# button.net
KiCad netlist of a schematic drawn in EAGLE
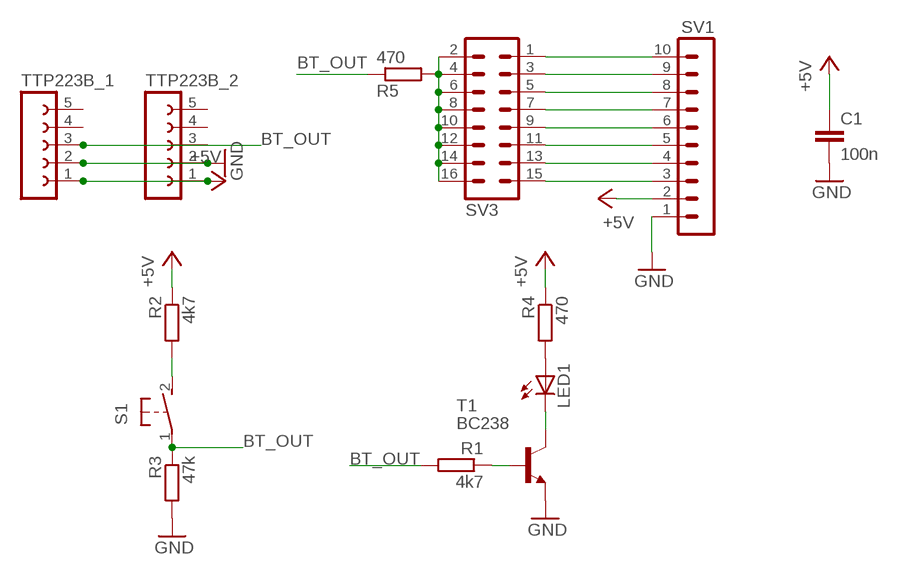
[diagram p0: schematic, sheet 1]

(export (version "E")
  (design (tool "Eeschema 10.0.6"))
  (components
    (comp (ref "C1")
      (value "100n")
      (footprint "eagle-import:C025-024X044")
      (libsource (lib "eagle-import") (part "C-EU025-024X044"))
    )
    (comp (ref "LED1")
      (value "LED5MM")
      (footprint "eagle-import:LED5MM")
      (libsource (lib "eagle-import") (part "LED5MM"))
    )
    (comp (ref "R1")
      (value "4k7")
      (footprint "eagle-import:0309_10")
      (libsource (lib "eagle-import") (part "R-EU_0309/10"))
    )
    (comp (ref "R2")
      (value "4k7")
      (footprint "eagle-import:R0805")
      (libsource (lib "eagle-import") (part "R-EU_R0805"))
    )
    (comp (ref "R3")
      (value "47k")
      (footprint "eagle-import:0414_15")
      (libsource (lib "eagle-import") (part "R-EU_0414/15"))
    )
    (comp (ref "R4")
      (value "470")
      (footprint "eagle-import:0207_7")
      (libsource (lib "eagle-import") (part "R-EU_0207/7"))
    )
    (comp (ref "R5")
      (value "470")
      (footprint "eagle-import:0207_7")
      (libsource (lib "eagle-import") (part "R-EU_0207/7"))
    )
    (comp (ref "S1")
      (value "31-XX")
      (footprint "eagle-import:B3F-31XX")
      (fields (field (name "MPN") "B3F-3100"))
      (libsource (lib "eagle-import") (part "31-XX"))
    )
    (comp (ref "SV1")
      (value "MA10-1W")
      (footprint "eagle-import:MA10-1W")
      (libsource (lib "eagle-import") (part "MA10-1W"))
    )
    (comp (ref "SV3")
      (value "MA08-2")
      (footprint "eagle-import:MA08-2")
      (libsource (lib "eagle-import") (part "MA08-2"))
    )
    (comp (ref "T1")
      (value "BC238")
      (footprint "eagle-import:TO5")
      (libsource (lib "eagle-import") (part "-NPN-TO5"))
    )
    (comp (ref "TTP223B_1")
      (value "FE05-1")
      (footprint "eagle-import:FE05-1")
      (libsource (lib "eagle-import") (part "FE05-1"))
    )
    (comp (ref "TTP223B_2")
      (value "FE05W")
      (footprint "eagle-import:FE05W")
      (libsource (lib "eagle-import") (part "FE05W"))
    )
  )
  (nets
    (net (code "1") (name "+5V") (class "Default")
      (node (ref "C1") (pin "1") (pinfunction "1_1") (pintype "passive"))
      (node (ref "R2") (pin "1") (pinfunction "1_1") (pintype "passive"))
      (node (ref "R4") (pin "1") (pinfunction "1_1") (pintype "passive"))
      (node (ref "SV1") (pin "2") (pinfunction "2_2") (pintype "passive"))
      (node (ref "TTP223B_1") (pin "1") (pinfunction "1_1") (pintype "passive"))
      (node (ref "TTP223B_2") (pin "1") (pinfunction "1_1") (pintype "passive"))
    )
    (net (code "2") (name "/BT_OUT") (class "Default")
      (node (ref "R1") (pin "2") (pinfunction "2_2") (pintype "passive"))
      (node (ref "R3") (pin "1") (pinfunction "1_1") (pintype "passive"))
      (node (ref "R5") (pin "1") (pinfunction "1_1") (pintype "passive"))
      (node (ref "S1") (pin "1") (pinfunction "P_1") (pintype "passive"))
      (node (ref "TTP223B_1") (pin "3") (pinfunction "3_3") (pintype "passive"))
      (node (ref "TTP223B_2") (pin "3") (pinfunction "3_3") (pintype "passive"))
    )
    (net (code "3") (name "GND") (class "Default")
      (node (ref "C1") (pin "2") (pinfunction "2_2") (pintype "passive"))
      (node (ref "R3") (pin "2") (pinfunction "2_2") (pintype "passive"))
      (node (ref "SV1") (pin "1") (pinfunction "1_1") (pintype "passive"))
      (node (ref "T1") (pin "1") (pinfunction "E_1") (pintype "passive"))
      (node (ref "TTP223B_1") (pin "2") (pinfunction "2_2") (pintype "passive"))
      (node (ref "TTP223B_2") (pin "2") (pinfunction "2_2") (pintype "passive"))
    )
    (net (code "4") (name "Net-(LED1-C)") (class "Default")
      (node (ref "LED1") (pin "K") (pinfunction "C_K") (pintype "passive"))
      (node (ref "T1") (pin "3") (pinfunction "C_3") (pintype "passive"))
    )
    (net (code "5") (name "Net-(LED1-PadA)") (class "Default")
      (node (ref "LED1") (pin "A") (pinfunction "A_A") (pintype "passive"))
      (node (ref "R4") (pin "2") (pinfunction "2_2") (pintype "passive"))
    )
    (net (code "6") (name "Net-(R5-Pad2)") (class "Default")
      (node (ref "R5") (pin "2") (pinfunction "2_2") (pintype "passive"))
      (node (ref "SV3") (pin "10") (pinfunction "10_10") (pintype "passive"))
      (node (ref "SV3") (pin "12") (pinfunction "12_12") (pintype "passive"))
      (node (ref "SV3") (pin "14") (pinfunction "14_14") (pintype "passive"))
      (node (ref "SV3") (pin "16") (pinfunction "16_16") (pintype "passive"))
      (node (ref "SV3") (pin "2") (pinfunction "2_2") (pintype "passive"))
      (node (ref "SV3") (pin "4") (pinfunction "4_4") (pintype "passive"))
      (node (ref "SV3") (pin "6") (pinfunction "6_6") (pintype "passive"))
      (node (ref "SV3") (pin "8") (pinfunction "8_8") (pintype "passive"))
    )
    (net (code "7") (name "Net-(S1-S)") (class "Default")
      (node (ref "R2") (pin "2") (pinfunction "2_2") (pintype "passive"))
      (node (ref "S1") (pin "2") (pinfunction "S_2") (pintype "passive"))
    )
    (net (code "8") (name "Net-(SV1-Pad3)") (class "Default")
      (node (ref "SV1") (pin "3") (pinfunction "3_3") (pintype "passive"))
      (node (ref "SV3") (pin "15") (pinfunction "15_15") (pintype "passive"))
    )
    (net (code "9") (name "Net-(SV1-Pad4)") (class "Default")
      (node (ref "SV1") (pin "4") (pinfunction "4_4") (pintype "passive"))
      (node (ref "SV3") (pin "13") (pinfunction "13_13") (pintype "passive"))
    )
    (net (code "10") (name "Net-(SV1-Pad5)") (class "Default")
      (node (ref "SV1") (pin "5") (pinfunction "5_5") (pintype "passive"))
      (node (ref "SV3") (pin "11") (pinfunction "11_11") (pintype "passive"))
    )
    (net (code "11") (name "Net-(SV1-Pad6)") (class "Default")
      (node (ref "SV1") (pin "6") (pinfunction "6_6") (pintype "passive"))
      (node (ref "SV3") (pin "9") (pinfunction "9_9") (pintype "passive"))
    )
    (net (code "12") (name "Net-(SV1-Pad7)") (class "Default")
      (node (ref "SV1") (pin "7") (pinfunction "7_7") (pintype "passive"))
      (node (ref "SV3") (pin "7") (pinfunction "7_7") (pintype "passive"))
    )
    (net (code "13") (name "Net-(SV1-Pad8)") (class "Default")
      (node (ref "SV1") (pin "8") (pinfunction "8_8") (pintype "passive"))
      (node (ref "SV3") (pin "5") (pinfunction "5_5") (pintype "passive"))
    )
    (net (code "14") (name "Net-(SV1-Pad9)") (class "Default")
      (node (ref "SV1") (pin "9") (pinfunction "9_9") (pintype "passive"))
      (node (ref "SV3") (pin "3") (pinfunction "3_3") (pintype "passive"))
    )
    (net (code "15") (name "Net-(SV1-Pad10)") (class "Default")
      (node (ref "SV1") (pin "10") (pinfunction "10_10") (pintype "passive"))
      (node (ref "SV3") (pin "1") (pinfunction "1_1") (pintype "passive"))
    )
    (net (code "16") (name "Net-(T1-B)") (class "Default")
      (node (ref "R1") (pin "1") (pinfunction "1_1") (pintype "passive"))
      (node (ref "T1") (pin "2") (pinfunction "B_2") (pintype "passive"))
    )
    (net (code "17") (name "unconnected-(TTP223B_1-Pad4)") (class "Default")
      (node (ref "TTP223B_1") (pin "4") (pinfunction "4_4") (pintype "passive"))
    )
    (net (code "18") (name "unconnected-(TTP223B_1-Pad5)") (class "Default")
      (node (ref "TTP223B_1") (pin "5") (pinfunction "5_5") (pintype "passive"))
    )
    (net (code "19") (name "unconnected-(TTP223B_2-Pad4)") (class "Default")
      (node (ref "TTP223B_2") (pin "4") (pinfunction "4_4") (pintype "passive"))
    )
    (net (code "20") (name "unconnected-(TTP223B_2-Pad5)") (class "Default")
      (node (ref "TTP223B_2") (pin "5") (pinfunction "5_5") (pintype "passive"))
    )
  )
)
